# I2C.net
KiCad netlist of a schematic drawn in Altium Designer
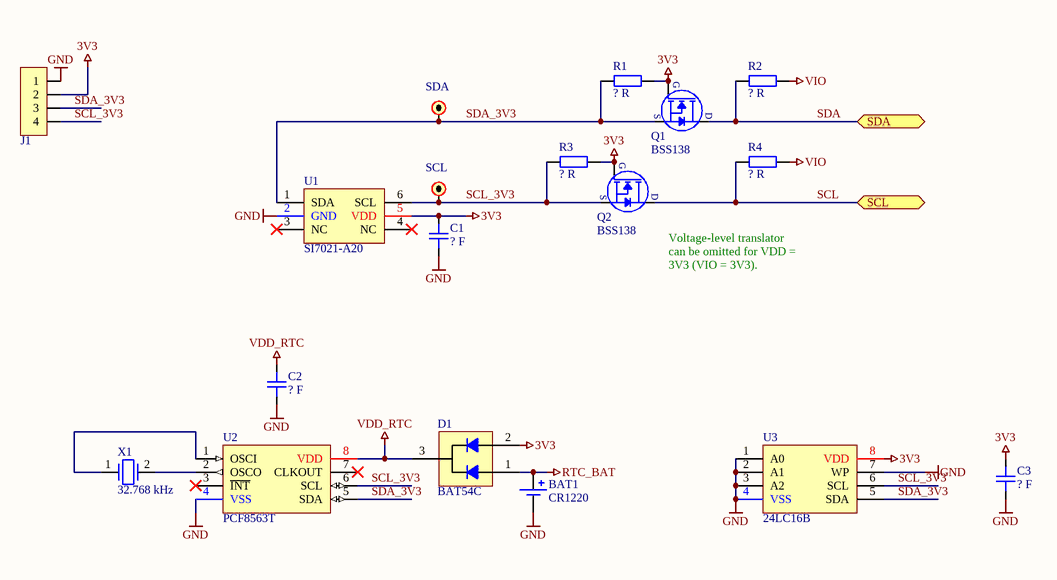
[diagram p0: I2C.SchDoc]

(export (version "E")
  (design (tool "Eeschema 10.0.6"))
  (components
    (comp (ref "BAT1")
      (value "CR1220")
      (footprint "BC501SM")
      (description "Single Cell Battery")
      (libsource (lib "AG.Holder") (part "BC501SM"))
    )
    (comp (ref "C1")
      (value "? F")
      (footprint "0603C_RF_M")
      (description "Capacitor")
      (fields (field (name "TOLERANCE") "?") (field (name "MANUFACTURER") "Generic Brand"))
      (libsource (lib "AG.Generic") (part "C"))
    )
    (comp (ref "C2")
      (value "? F")
      (footprint "0603C_RF_M")
      (description "Capacitor")
      (fields (field (name "TOLERANCE") "?") (field (name "MANUFACTURER") "Generic Brand"))
      (libsource (lib "AG.Generic") (part "C"))
    )
    (comp (ref "C3")
      (value "? F")
      (footprint "0603C_RF_M")
      (description "Capacitor")
      (fields (field (name "TOLERANCE") "?") (field (name "MANUFACTURER") "Generic Brand"))
      (libsource (lib "AG.Generic") (part "C"))
    )
    (comp (ref "D1")
      (value "BAT54C")
      (footprint "IRLML_SOT-23")
      (description "DIODE ARRAY SCHOTTKY COMM CATH 30V 0.2A SOT-23")
      (fields (field (name "PARTNO") "BAT54C-FDICT-ND") (field (name "MANUFACTURER") "Diodes Incorporated"))
      (libsource (lib "AG.Discrete") (part "BAT54C"))
    )
    (comp (ref "J1")
      (value "PINHDR-4P1")
      (footprint "AG.Connectors:HEADER-2.54-4P1")
      (description "Generic Pin Header 4x1")
      (libsource (lib "AG.Connectors") (part "PINHDR-4P1"))
    )
    (comp (ref "Q1")
      (value "BSS138")
      (footprint "IRLML_SOT-23")
      (description "MOSFET N-CH 50V 200MA SOT23")
      (fields
        (field (name "MANUFACTURER") "ON Semiconductor")
        (field (name "MANUFACTURER PART NO") "BSS138LT1G")
      )
      (libsource (lib "AG.Discrete") (part "BSS138"))
    )
    (comp (ref "Q2")
      (value "BSS138")
      (footprint "IRLML_SOT-23")
      (description "MOSFET N-CH 50V 200MA SOT23")
      (fields
        (field (name "MANUFACTURER") "ON Semiconductor")
        (field (name "MANUFACTURER PART NO") "BSS138LT1G")
      )
      (libsource (lib "AG.Discrete") (part "BSS138"))
    )
    (comp (ref "R1")
      (value "? R")
      (footprint "Chip:R0603_RF_M")
      (description "Resistor")
      (fields (field (name "TOLERANCE") "?") (field (name "MANUFACTURER") "Generic Brand"))
      (libsource (lib "AG.Generic") (part "R"))
    )
    (comp (ref "R2")
      (value "? R")
      (footprint "Chip:R0603_RF_M")
      (description "Resistor")
      (fields (field (name "TOLERANCE") "?") (field (name "MANUFACTURER") "Generic Brand"))
      (libsource (lib "AG.Generic") (part "R"))
    )
    (comp (ref "R3")
      (value "? R")
      (footprint "Chip:R0603_RF_M")
      (description "Resistor")
      (fields (field (name "TOLERANCE") "?") (field (name "MANUFACTURER") "Generic Brand"))
      (libsource (lib "AG.Generic") (part "R"))
    )
    (comp (ref "R4")
      (value "? R")
      (footprint "Chip:R0603_RF_M")
      (description "Resistor")
      (fields (field (name "TOLERANCE") "?") (field (name "MANUFACTURER") "Generic Brand"))
      (libsource (lib "AG.Generic") (part "R"))
    )
    (comp (ref "TP1")
      (value "SDA")
      (footprint "PAD_R_1MM")
      (description "Test Point / Pad")
      (libsource (lib "AG.Misc") (part "Test Point"))
    )
    (comp (ref "TP2")
      (value "SCL")
      (footprint "PAD_R_1MM")
      (description "Test Point / Pad")
      (libsource (lib "AG.Misc") (part "Test Point"))
    )
    (comp (ref "U1")
      (value "SI7021-A20")
      (footprint "SI7021_DFN-6_RF_M")
      (description "SENS HUMID/TEMP 3.6V I2C 2% 6DFN")
      (fields (field (name "MANUFACTURER") "Silicon Labs"))
      (libsource (lib "AG.IC") (part "SI7021-A20"))
    )
    (comp (ref "U2") (value "PCF8563T") (footprint "SOIC-8") (libsource (lib "AG.IC") (part "PCF8563T")))
    (comp (ref "U3") (value "24LC16B") (footprint "AG.IC:SOIC-8") (libsource (lib "AG.IC") (part "24LC16B")))
    (comp (ref "X1")
      (value "32.768 kHz")
      (footprint "XTAL_3215")
      (description "Crystal Resonator (2 Leads)")
      (fields (field (name "MANUFACTURER") "Geyer") (field (name "MANUFACTURER PART NO") "KX-327NHT"))
      (libsource (lib "AG.Passive") (part "KX-327NHT"))
    )
  )
  (nets
    (net (code "1") (name "/SCL") (class "Default")
      (node (ref "Q2") (pin "3") (pinfunction "D_3") (pintype "passive"))
      (node (ref "R4") (pin "2") (pintype "passive"))
    )
    (net (code "2") (name "/SCL_3V3") (class "Default")
      (node (ref "J1") (pin "4") (pinfunction "4_4") (pintype "passive"))
      (node (ref "Q2") (pin "2") (pinfunction "S_2") (pintype "passive"))
      (node (ref "R3") (pin "2") (pintype "passive"))
      (node (ref "TP2") (pin "1") (pinfunction "1_1") (pintype "passive"))
      (node (ref "U1") (pin "6") (pinfunction "SCL_6") (pintype "passive"))
      (node (ref "U2") (pin "6") (pinfunction "SCL_6") (pintype "bidirectional"))
      (node (ref "U3") (pin "6") (pinfunction "SCL_6") (pintype "passive"))
    )
    (net (code "3") (name "/SDA") (class "Default")
      (node (ref "Q1") (pin "3") (pinfunction "D_3") (pintype "passive"))
      (node (ref "R2") (pin "1") (pintype "passive"))
    )
    (net (code "4") (name "/SDA_3V3") (class "Default")
      (node (ref "J1") (pin "3") (pinfunction "3_3") (pintype "passive"))
      (node (ref "Q1") (pin "2") (pinfunction "S_2") (pintype "passive"))
      (node (ref "R1") (pin "2") (pintype "passive"))
      (node (ref "TP1") (pin "1") (pinfunction "1_1") (pintype "passive"))
      (node (ref "U1") (pin "1") (pinfunction "SDA_1") (pintype "passive"))
      (node (ref "U2") (pin "5") (pinfunction "SDA_5") (pintype "bidirectional"))
      (node (ref "U3") (pin "5") (pinfunction "SDA_5") (pintype "passive"))
    )
    (net (code "5") (name "3V3") (class "Default")
      (node (ref "C1") (pin "2") (pinfunction "2_2") (pintype "passive"))
      (node (ref "C3") (pin "2") (pinfunction "2_2") (pintype "passive"))
      (node (ref "D1") (pin "2") (pinfunction "A2_2") (pintype "passive"))
      (node (ref "J1") (pin "2") (pinfunction "2_2") (pintype "passive"))
      (node (ref "Q1") (pin "1") (pinfunction "G_1") (pintype "passive"))
      (node (ref "Q2") (pin "1") (pinfunction "G_1") (pintype "passive"))
      (node (ref "R1") (pin "1") (pintype "passive"))
      (node (ref "R3") (pin "1") (pintype "passive"))
      (node (ref "U1") (pin "5") (pinfunction "VDD_5") (pintype "passive"))
      (node (ref "U3") (pin "8") (pinfunction "VDD_8") (pintype "passive"))
    )
    (net (code "6") (name "GND") (class "Default")
      (node (ref "BAT1") (pin "N") (pinfunction "N_N") (pintype "power_in"))
      (node (ref "C1") (pin "1") (pinfunction "1_1") (pintype "passive"))
      (node (ref "C2") (pin "1") (pinfunction "1_1") (pintype "passive"))
      (node (ref "C3") (pin "1") (pinfunction "1_1") (pintype "passive"))
      (node (ref "J1") (pin "1") (pinfunction "1_1") (pintype "passive"))
      (node (ref "U1") (pin "2") (pinfunction "GND_2") (pintype "passive"))
      (node (ref "U2") (pin "4") (pinfunction "VSS_4") (pintype "power_in"))
      (node (ref "U3") (pin "1") (pinfunction "A0_1") (pintype "passive"))
      (node (ref "U3") (pin "2") (pinfunction "A1_2") (pintype "passive"))
      (node (ref "U3") (pin "3") (pinfunction "A2_3") (pintype "passive"))
      (node (ref "U3") (pin "4") (pinfunction "VSS_4") (pintype "passive"))
      (node (ref "U3") (pin "7") (pinfunction "WP_7") (pintype "passive"))
    )
    (net (code "7") (name "Net-(U2-OSCI)") (class "Default")
      (node (ref "U2") (pin "1") (pinfunction "OSCI_1") (pintype "input"))
      (node (ref "X1") (pin "1") (pinfunction "1_1") (pintype "passive"))
    )
    (net (code "8") (name "Net-(U2-OSCO)") (class "Default")
      (node (ref "U2") (pin "2") (pinfunction "OSCO_2") (pintype "output"))
      (node (ref "X1") (pin "2") (pinfunction "2_2") (pintype "passive"))
    )
    (net (code "9") (name "RTC_BAT") (class "Default")
      (node (ref "BAT1") (pin "P") (pinfunction "P_P") (pintype "power_in"))
      (node (ref "D1") (pin "1") (pinfunction "A1_1") (pintype "passive"))
    )
    (net (code "10") (name "VDD_RTC") (class "Default")
      (node (ref "C2") (pin "2") (pinfunction "2_2") (pintype "passive"))
      (node (ref "D1") (pin "3") (pinfunction "C_3") (pintype "passive"))
      (node (ref "U2") (pin "8") (pinfunction "VDD_8") (pintype "power_in"))
    )
    (net (code "11") (name "VIO") (class "Default")
      (node (ref "R2") (pin "2") (pintype "passive"))
      (node (ref "R4") (pin "1") (pintype "passive"))
    )
    (net (code "12") (name "unconnected-(U1-NC-Pad3)") (class "Default")
      (node (ref "U1") (pin "3") (pinfunction "NC_3") (pintype "passive+no_connect"))
    )
    (net (code "13") (name "unconnected-(U1-NC-Pad4)") (class "Default")
      (node (ref "U1") (pin "4") (pinfunction "NC_4") (pintype "passive+no_connect"))
    )
    (net (code "14") (name "unconnected-(U2-CLKOUT-Pad7)") (class "Default")
      (node (ref "U2") (pin "7") (pinfunction "CLKOUT_7") (pintype "open_collector+no_connect"))
    )
    (net (code "15") (name "unconnected-(U2-~{INT}-Pad3)") (class "Default")
      (node (ref "U2") (pin "3") (pinfunction "~{INT}_3") (pintype "open_collector+no_connect"))
    )
  )
)
